# irsm-v1.net
KiCad netlist of a schematic drawn in EAGLE
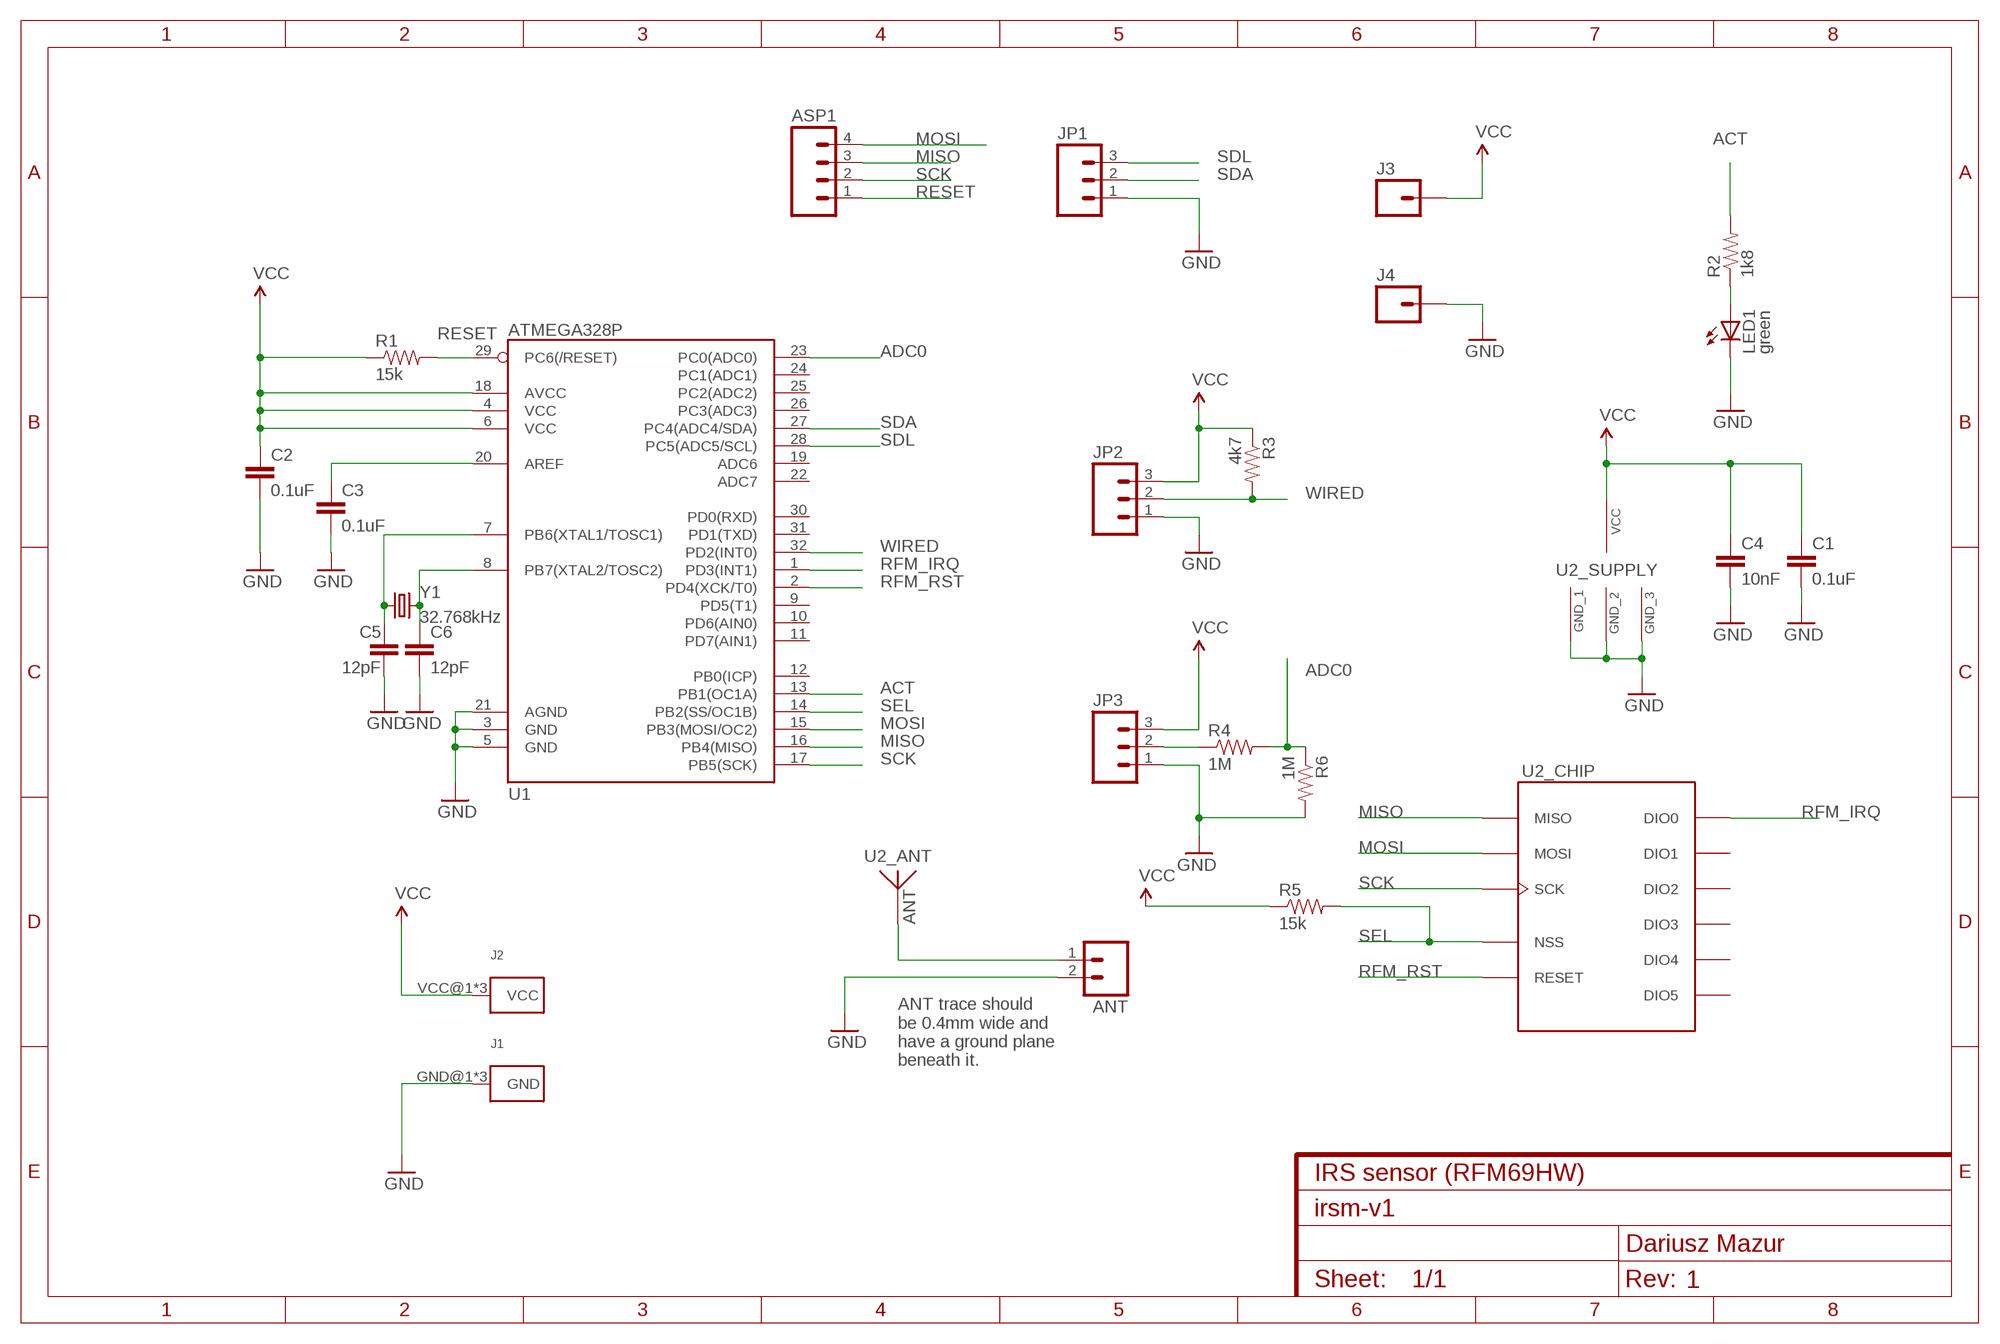
[diagram p0: schematic, sheet 1]

(export (version "E")
  (design (tool "Eeschema 10.0.6"))
  (components
    (comp (ref "ANT")
      (value "M02PTH3")
      (footprint "eagle-import:1X02_LONGPADS")
      (libsource (lib "eagle-import") (part "M02PTH3"))
    )
    (comp (ref "ASP1")
      (value "M04PTH")
      (footprint "eagle-import:1X04")
      (libsource (lib "eagle-import") (part "M04PTH"))
    )
    (comp (ref "C1")
      (value "0.1uF")
      (footprint "eagle-import:0603-CAP")
      (libsource (lib "eagle-import") (part "0.1UF-25V(+80/-20%)(0603)"))
    )
    (comp (ref "C2")
      (value "0.1uF")
      (footprint "eagle-import:0603-CAP")
      (libsource (lib "eagle-import") (part "0.1UF-25V(+80/-20%)(0603)"))
    )
    (comp (ref "C3")
      (value "0.1uF")
      (footprint "eagle-import:0603-CAP")
      (libsource (lib "eagle-import") (part "0.1UF-25V(+80/-20%)(0603)"))
    )
    (comp (ref "C4")
      (value "10nF")
      (footprint "eagle-import:0603-CAP")
      (libsource (lib "eagle-import") (part "CAP0603-CAP"))
    )
    (comp (ref "C5")
      (value "12pF")
      (footprint "eagle-import:0603-CAP")
      (libsource (lib "eagle-import") (part "12PF-50V-5%(0603)"))
    )
    (comp (ref "C6")
      (value "12pF")
      (footprint "eagle-import:0603-CAP")
      (libsource (lib "eagle-import") (part "12PF-50V-5%(0603)"))
    )
    (comp (ref "J1")
      (value "KEYSTONE-629")
      (footprint "eagle-import:KEYSTONE_AA_AAA_BATTERY_TERMINAL-629")
      (libsource (lib "eagle-import") (part "KEYSTONE-629"))
    )
    (comp (ref "J2")
      (value "KEYSTONE-637")
      (footprint "eagle-import:KEYSTONE_AA_AAA_BATTERY_TERMINAL-637")
      (libsource (lib "eagle-import") (part "KEYSTONE-637"))
    )
    (comp (ref "J3")
      (value "M01PTH")
      (footprint "eagle-import:1X01")
      (libsource (lib "eagle-import") (part "M01PTH"))
    )
    (comp (ref "J4")
      (value "M01PTH")
      (footprint "eagle-import:1X01")
      (libsource (lib "eagle-import") (part "M01PTH"))
    )
    (comp (ref "JP1")
      (value "M03PTH")
      (footprint "eagle-import:1X03")
      (libsource (lib "eagle-import") (part "M03PTH"))
    )
    (comp (ref "JP2")
      (value "M03PTH")
      (footprint "eagle-import:1X03")
      (libsource (lib "eagle-import") (part "M03PTH"))
    )
    (comp (ref "JP3")
      (value "M03PTH")
      (footprint "eagle-import:1X03")
      (libsource (lib "eagle-import") (part "M03PTH"))
    )
    (comp (ref "LED1")
      (value "green")
      (footprint "eagle-import:LED-0603")
      (libsource (lib "eagle-import") (part "LED0603"))
    )
    (comp (ref "R1")
      (value "15k")
      (footprint "eagle-import:0603-RES")
      (libsource (lib "eagle-import") (part "RESISTOR0603-RES"))
    )
    (comp (ref "R2")
      (value "1k8")
      (footprint "eagle-import:0603-RES")
      (libsource (lib "eagle-import") (part "RESISTOR0603-RES"))
    )
    (comp (ref "R3")
      (value "4k7")
      (footprint "eagle-import:0603-RES")
      (libsource (lib "eagle-import") (part "RESISTOR0603-RES"))
    )
    (comp (ref "R4")
      (value "1M")
      (footprint "eagle-import:0603-RES")
      (libsource (lib "eagle-import") (part "RESISTOR0603-RES"))
    )
    (comp (ref "R5")
      (value "15k")
      (footprint "eagle-import:0603-RES")
      (libsource (lib "eagle-import") (part "RESISTOR0603-RES"))
    )
    (comp (ref "R6")
      (value "1M")
      (footprint "eagle-import:0603-RES")
      (libsource (lib "eagle-import") (part "RESISTOR0603-RES"))
    )
    (comp (ref "U1")
      (value "ATMEGA328P")
      (footprint "eagle-import:TQFP32-08")
      (libsource (lib "eagle-import") (part "ATMEGA328_SMT"))
    )
    (comp (ref "U2")
      (value "RFM69HCW-S2")
      (footprint "eagle-import:HOPE-RF-16")
      (libsource (lib "eagle-import") (part "RFM69HCW-S2"))
    )
    (comp (ref "Y1")
      (value "32.768kHz")
      (footprint "eagle-import:CRYSTAL-SMD-3.2X1.5MM")
      (libsource (lib "eagle-import") (part "CRYSTAL3.2X1.5MM"))
    )
  )
  (nets
    (net (code "1") (name "/ACT") (class "Default")
      (node (ref "R2") (pin "2") (pinfunction "2_2") (pintype "passive"))
      (node (ref "U1") (pin "13") (pinfunction "PB1(OC1A)_13") (pintype "bidirectional"))
    )
    (net (code "2") (name "/ADC0") (class "Default")
      (node (ref "R4") (pin "2") (pinfunction "2_2") (pintype "passive"))
      (node (ref "R6") (pin "1") (pinfunction "1_1") (pintype "passive"))
      (node (ref "U1") (pin "23") (pinfunction "PC0(ADC0)_23") (pintype "bidirectional"))
    )
    (net (code "3") (name "/MISO") (class "Default")
      (node (ref "ASP1") (pin "3") (pinfunction "3_3") (pintype "passive"))
      (node (ref "U1") (pin "16") (pinfunction "PB4(MISO)_16") (pintype "bidirectional"))
      (node (ref "U2") (pin "MISO") (pinfunction "MISO_MISO") (pintype "input"))
    )
    (net (code "4") (name "/MOSI") (class "Default")
      (node (ref "ASP1") (pin "4") (pinfunction "4_4") (pintype "passive"))
      (node (ref "U1") (pin "15") (pinfunction "PB3(MOSI/OC2)_15") (pintype "bidirectional"))
      (node (ref "U2") (pin "MOSI") (pinfunction "MOSI_MOSI") (pintype "output"))
    )
    (net (code "5") (name "/RESET") (class "Default")
      (node (ref "ASP1") (pin "1") (pinfunction "1_1") (pintype "passive"))
      (node (ref "R1") (pin "2") (pinfunction "2_2") (pintype "passive"))
      (node (ref "U1") (pin "29") (pinfunction "PC6(/RESET)_29") (pintype "bidirectional"))
    )
    (net (code "6") (name "/RFM_IRQ") (class "Default")
      (node (ref "U1") (pin "1") (pinfunction "PD3(INT1)_1") (pintype "bidirectional"))
      (node (ref "U2") (pin "DIO0") (pinfunction "DIO0_DIO0") (pintype "bidirectional"))
    )
    (net (code "7") (name "/RFM_RST") (class "Default")
      (node (ref "U1") (pin "2") (pinfunction "PD4(XCK/T0)_2") (pintype "bidirectional"))
      (node (ref "U2") (pin "RESET") (pinfunction "RESET_RESET") (pintype "bidirectional"))
    )
    (net (code "8") (name "/SCK") (class "Default")
      (node (ref "ASP1") (pin "2") (pinfunction "2_2") (pintype "passive"))
      (node (ref "U1") (pin "17") (pinfunction "PB5(SCK)_17") (pintype "bidirectional"))
      (node (ref "U2") (pin "SCK") (pinfunction "SCK_SCK") (pintype "input"))
    )
    (net (code "9") (name "/SDA") (class "Default")
      (node (ref "JP1") (pin "2") (pinfunction "2_2") (pintype "passive"))
      (node (ref "U1") (pin "27") (pinfunction "PC4(ADC4/SDA)_27") (pintype "bidirectional"))
    )
    (net (code "10") (name "/SDL") (class "Default")
      (node (ref "JP1") (pin "3") (pinfunction "3_3") (pintype "passive"))
      (node (ref "U1") (pin "28") (pinfunction "PC5(ADC5/SCL)_28") (pintype "bidirectional"))
    )
    (net (code "11") (name "/SEL") (class "Default")
      (node (ref "R5") (pin "2") (pinfunction "2_2") (pintype "passive"))
      (node (ref "U1") (pin "14") (pinfunction "PB2(SS/OC1B)_14") (pintype "bidirectional"))
      (node (ref "U2") (pin "NSS") (pinfunction "NSS_NSS") (pintype "input"))
    )
    (net (code "12") (name "/WIRED") (class "Default")
      (node (ref "JP2") (pin "2") (pinfunction "2_2") (pintype "passive"))
      (node (ref "R3") (pin "2") (pinfunction "2_2") (pintype "passive"))
      (node (ref "U1") (pin "32") (pinfunction "PD2(INT0)_32") (pintype "bidirectional"))
    )
    (net (code "13") (name "GND") (class "Default")
      (node (ref "ANT") (pin "2") (pinfunction "2_2") (pintype "passive"))
      (node (ref "C1") (pin "2") (pinfunction "2_2") (pintype "passive"))
      (node (ref "C2") (pin "2") (pinfunction "2_2") (pintype "passive"))
      (node (ref "C3") (pin "2") (pinfunction "2_2") (pintype "passive"))
      (node (ref "C4") (pin "2") (pinfunction "2_2") (pintype "passive"))
      (node (ref "C5") (pin "2") (pinfunction "2_2") (pintype "passive"))
      (node (ref "C6") (pin "2") (pinfunction "2_2") (pintype "passive"))
      (node (ref "J1") (pin "GND@1") (pinfunction "GND_GND@1") (pintype "power_in"))
      (node (ref "J1") (pin "GND@2") (pinfunction "GND_GND@2") (pintype "power_in"))
      (node (ref "J1") (pin "GND@3") (pinfunction "GND_GND@3") (pintype "power_in"))
      (node (ref "J4") (pin "1") (pinfunction "1_1") (pintype "passive"))
      (node (ref "JP1") (pin "1") (pinfunction "1_1") (pintype "passive"))
      (node (ref "JP2") (pin "1") (pinfunction "1_1") (pintype "passive"))
      (node (ref "JP3") (pin "1") (pinfunction "1_1") (pintype "passive"))
      (node (ref "LED1") (pin "C") (pinfunction "C_C") (pintype "passive"))
      (node (ref "R6") (pin "2") (pinfunction "2_2") (pintype "passive"))
      (node (ref "U1") (pin "21") (pinfunction "AGND_21") (pintype "bidirectional"))
      (node (ref "U1") (pin "3") (pinfunction "GND_3") (pintype "bidirectional"))
      (node (ref "U1") (pin "5") (pinfunction "GND_5") (pintype "bidirectional"))
      (node (ref "U2") (pin "GND1") (pinfunction "GND_1_GND1") (pintype "power_in"))
      (node (ref "U2") (pin "GND2") (pinfunction "GND_2_GND2") (pintype "power_in"))
      (node (ref "U2") (pin "GND3") (pinfunction "GND_3_GND3") (pintype "power_in"))
    )
    (net (code "14") (name "Net-(ANT-Pad1)") (class "Default")
      (node (ref "ANT") (pin "1") (pinfunction "1_1") (pintype "passive"))
      (node (ref "U2") (pin "ANT") (pinfunction "ANT_ANT") (pintype "passive"))
    )
    (net (code "15") (name "Net-(JP3-Pad2)") (class "Default")
      (node (ref "JP3") (pin "2") (pinfunction "2_2") (pintype "passive"))
      (node (ref "R4") (pin "1") (pinfunction "1_1") (pintype "passive"))
    )
    (net (code "16") (name "Net-(LED1-PadA)") (class "Default")
      (node (ref "LED1") (pin "A") (pinfunction "A_A") (pintype "passive"))
      (node (ref "R2") (pin "1") (pinfunction "1_1") (pintype "passive"))
    )
    (net (code "17") (name "Net-(U1-AREF)") (class "Default")
      (node (ref "C3") (pin "1") (pinfunction "1_1") (pintype "passive"))
      (node (ref "U1") (pin "20") (pinfunction "AREF_20") (pintype "bidirectional"))
    )
    (net (code "18") (name "Net-(U1-PB6(XTAL1{slash}TOSC1))") (class "Default")
      (node (ref "C5") (pin "1") (pinfunction "1_1") (pintype "passive"))
      (node (ref "U1") (pin "7") (pinfunction "PB6(XTAL1/TOSC1)_7") (pintype "bidirectional"))
      (node (ref "Y1") (pin "P$1") (pinfunction "1_P$1") (pintype "passive"))
    )
    (net (code "19") (name "Net-(U1-PB7(XTAL2{slash}TOSC2))") (class "Default")
      (node (ref "C6") (pin "1") (pinfunction "1_1") (pintype "passive"))
      (node (ref "U1") (pin "8") (pinfunction "PB7(XTAL2/TOSC2)_8") (pintype "bidirectional"))
      (node (ref "Y1") (pin "P$2") (pinfunction "2_P$2") (pintype "passive"))
    )
    (net (code "20") (name "VCC") (class "Default")
      (node (ref "C1") (pin "1") (pinfunction "1_1") (pintype "passive"))
      (node (ref "C2") (pin "1") (pinfunction "1_1") (pintype "passive"))
      (node (ref "C4") (pin "1") (pinfunction "1_1") (pintype "passive"))
      (node (ref "J2") (pin "VCC@1") (pinfunction "VCC_VCC@1") (pintype "power_in"))
      (node (ref "J2") (pin "VCC@2") (pinfunction "VCC_VCC@2") (pintype "power_in"))
      (node (ref "J2") (pin "VCC@3") (pinfunction "VCC_VCC@3") (pintype "power_in"))
      (node (ref "J3") (pin "1") (pinfunction "1_1") (pintype "passive"))
      (node (ref "JP2") (pin "3") (pinfunction "3_3") (pintype "passive"))
      (node (ref "JP3") (pin "3") (pinfunction "3_3") (pintype "passive"))
      (node (ref "R1") (pin "1") (pinfunction "1_1") (pintype "passive"))
      (node (ref "R3") (pin "1") (pinfunction "1_1") (pintype "passive"))
      (node (ref "R5") (pin "1") (pinfunction "1_1") (pintype "passive"))
      (node (ref "U1") (pin "18") (pinfunction "AVCC_18") (pintype "bidirectional"))
      (node (ref "U1") (pin "4") (pinfunction "VCC_4") (pintype "bidirectional"))
      (node (ref "U1") (pin "6") (pinfunction "VCC_6") (pintype "bidirectional"))
      (node (ref "U2") (pin "3.3V") (pinfunction "VCC_3.3V") (pintype "power_in"))
    )
    (net (code "21") (name "unconnected-(U1-ADC6-Pad19)") (class "Default")
      (node (ref "U1") (pin "19") (pinfunction "ADC6_19") (pintype "bidirectional"))
    )
    (net (code "22") (name "unconnected-(U1-ADC7-Pad22)") (class "Default")
      (node (ref "U1") (pin "22") (pinfunction "ADC7_22") (pintype "bidirectional"))
    )
    (net (code "23") (name "unconnected-(U1-PB0(ICP)-Pad12)") (class "Default")
      (node (ref "U1") (pin "12") (pinfunction "PB0(ICP)_12") (pintype "bidirectional"))
    )
    (net (code "24") (name "unconnected-(U1-PC1(ADC1)-Pad24)") (class "Default")
      (node (ref "U1") (pin "24") (pinfunction "PC1(ADC1)_24") (pintype "bidirectional"))
    )
    (net (code "25") (name "unconnected-(U1-PC2(ADC2)-Pad25)") (class "Default")
      (node (ref "U1") (pin "25") (pinfunction "PC2(ADC2)_25") (pintype "bidirectional"))
    )
    (net (code "26") (name "unconnected-(U1-PC3(ADC3)-Pad26)") (class "Default")
      (node (ref "U1") (pin "26") (pinfunction "PC3(ADC3)_26") (pintype "bidirectional"))
    )
    (net (code "27") (name "unconnected-(U1-PD0(RXD)-Pad30)") (class "Default")
      (node (ref "U1") (pin "30") (pinfunction "PD0(RXD)_30") (pintype "bidirectional"))
    )
    (net (code "28") (name "unconnected-(U1-PD1(TXD)-Pad31)") (class "Default")
      (node (ref "U1") (pin "31") (pinfunction "PD1(TXD)_31") (pintype "bidirectional"))
    )
    (net (code "29") (name "unconnected-(U1-PD5(T1)-Pad9)") (class "Default")
      (node (ref "U1") (pin "9") (pinfunction "PD5(T1)_9") (pintype "bidirectional"))
    )
    (net (code "30") (name "unconnected-(U1-PD6(AIN0)-Pad10)") (class "Default")
      (node (ref "U1") (pin "10") (pinfunction "PD6(AIN0)_10") (pintype "bidirectional"))
    )
    (net (code "31") (name "unconnected-(U1-PD7(AIN1)-Pad11)") (class "Default")
      (node (ref "U1") (pin "11") (pinfunction "PD7(AIN1)_11") (pintype "bidirectional"))
    )
    (net (code "32") (name "unconnected-(U2-PadDIO1)") (class "Default")
      (node (ref "U2") (pin "DIO1") (pinfunction "DIO1_DIO1") (pintype "bidirectional"))
    )
    (net (code "33") (name "unconnected-(U2-PadDIO2)") (class "Default")
      (node (ref "U2") (pin "DIO2") (pinfunction "DIO2_DIO2") (pintype "bidirectional"))
    )
    (net (code "34") (name "unconnected-(U2-PadDIO3)") (class "Default")
      (node (ref "U2") (pin "DIO3") (pinfunction "DIO3_DIO3") (pintype "bidirectional"))
    )
    (net (code "35") (name "unconnected-(U2-PadDIO4)") (class "Default")
      (node (ref "U2") (pin "DIO4") (pinfunction "DIO4_DIO4") (pintype "bidirectional"))
    )
    (net (code "36") (name "unconnected-(U2-PadDIO5)") (class "Default")
      (node (ref "U2") (pin "DIO5") (pinfunction "DIO5_DIO5") (pintype "bidirectional"))
    )
  )
)
